# design.net
KiCad netlist of a schematic drawn in Altium Designer
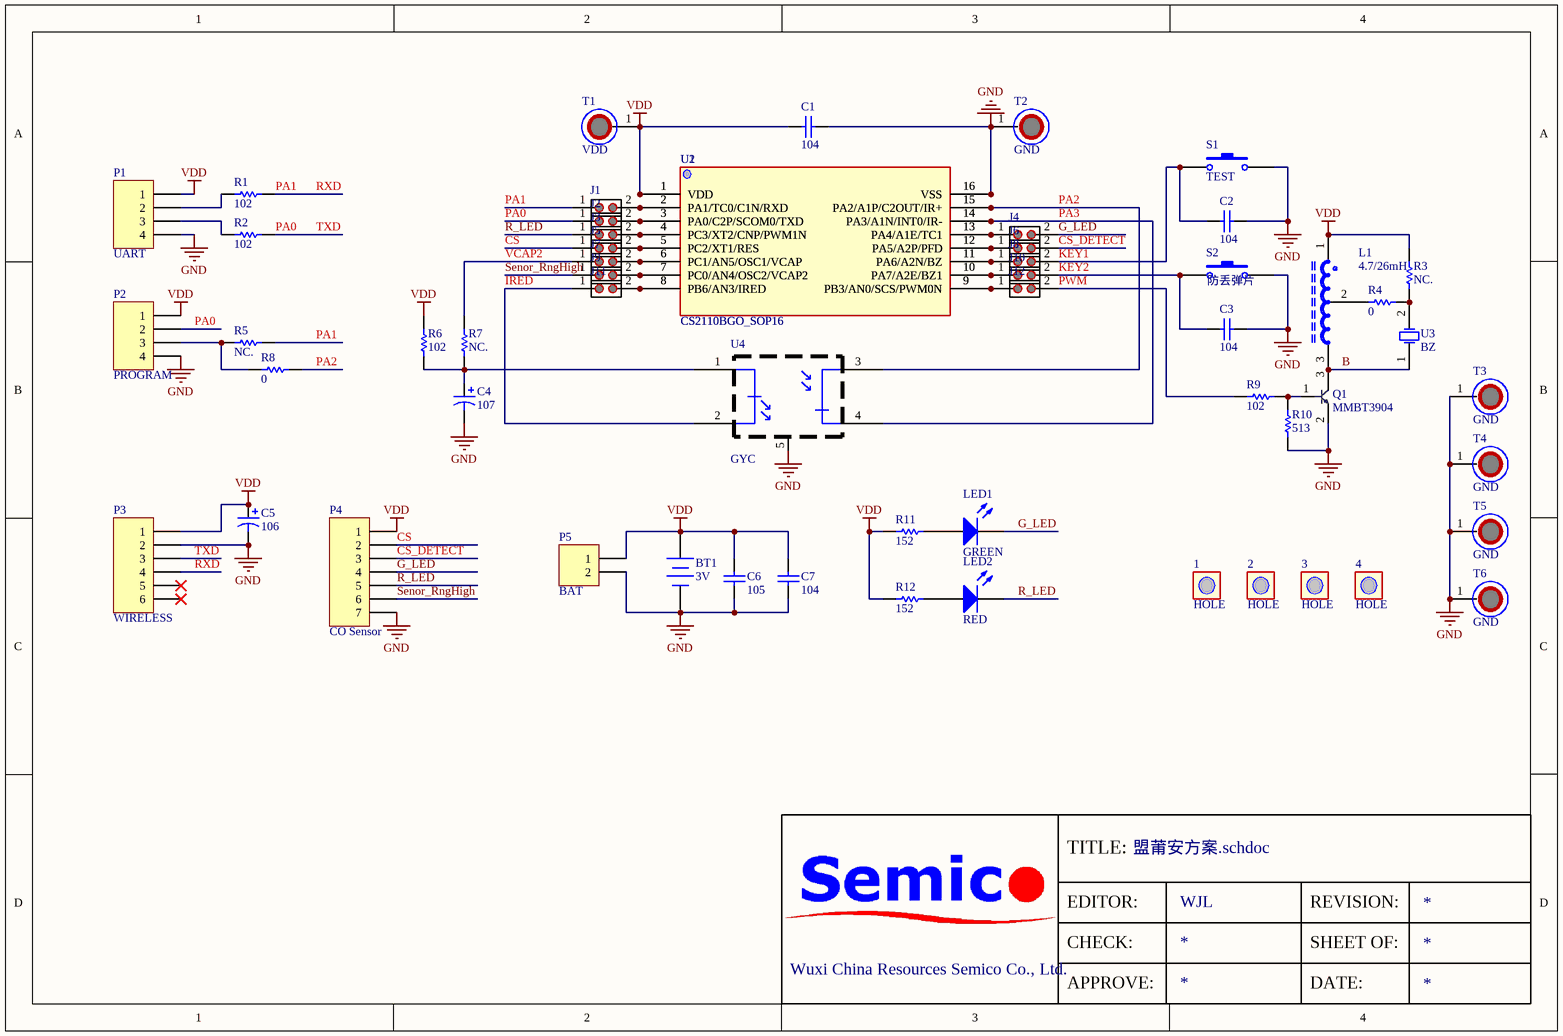
[diagram p0: 盟莆安方案.schdoc]

(export (version "E")
  (design (tool "Eeschema 10.0.6"))
  (components
    (comp (ref "1") (value "HOLE") (footprint "HOLE") (libsource (lib "原理图库") (part "HOLE")))
    (comp (ref "2") (value "HOLE") (footprint "HOLE") (libsource (lib "原理图库") (part "HOLE")))
    (comp (ref "3") (value "HOLE") (footprint "HOLE") (libsource (lib "原理图库") (part "HOLE")))
    (comp (ref "4") (value "HOLE") (footprint "HOLE") (libsource (lib "原理图库") (part "HOLE")))
    (comp (ref "BT1")
      (value "3V")
      (footprint "BAT-2")
      (description "Multicell Battery")
      (fields (field (name "PUBLISHER") "Altium Limited"))
      (libsource (lib "Miscellaneous Devices") (part "Battery"))
    )
    (comp (ref "C1")
      (value "104")
      (footprint "C0805")
      (description "Capacitor")
      (fields (field (name "PUBLISHER") "Altium Limited"))
      (libsource (lib "Miscellaneous Devices") (part "Cap"))
    )
    (comp (ref "C2")
      (value "104")
      (footprint "C0805")
      (description "Capacitor")
      (fields (field (name "PUBLISHER") "Altium Limited"))
      (libsource (lib "Miscellaneous Devices") (part "Cap"))
    )
    (comp (ref "C3")
      (value "104")
      (footprint "C0805")
      (description "Capacitor")
      (fields (field (name "PUBLISHER") "Altium Limited"))
      (libsource (lib "Miscellaneous Devices") (part "Cap"))
    )
    (comp (ref "C4")
      (value "107")
      (footprint "220UF/16V")
      (description "Polarized Capacitor (Radial)")
      (fields (field (name "PUBLISHER") "Altium Limited"))
      (libsource (lib "Miscellaneous Devices") (part "Cap Pol1"))
    )
    (comp (ref "C5")
      (value "106")
      (footprint "47UF/25V")
      (description "Polarized Capacitor (Radial)")
      (fields (field (name "PUBLISHER") "Altium Limited"))
      (libsource (lib "Miscellaneous Devices") (part "Cap Pol1"))
    )
    (comp (ref "C6")
      (value "105")
      (footprint "C0805")
      (description "Capacitor")
      (fields (field (name "PUBLISHER") "Altium Limited"))
      (libsource (lib "Miscellaneous Devices") (part "Cap"))
    )
    (comp (ref "C7")
      (value "104")
      (footprint "C0805")
      (description "Capacitor")
      (fields (field (name "PUBLISHER") "Altium Limited"))
      (libsource (lib "Miscellaneous Devices") (part "Cap"))
    )
    (comp (ref "J1") (value "~") (footprint "SIP2") (libsource (lib "原理图库") (part "JUMPER(SIP2)")))
    (comp (ref "J2") (value "~") (footprint "SIP2") (libsource (lib "原理图库") (part "JUMPER(SIP2)")))
    (comp (ref "J3") (value "~") (footprint "SIP2") (libsource (lib "原理图库") (part "JUMPER(SIP2)")))
    (comp (ref "J4") (value "~") (footprint "SIP2") (libsource (lib "原理图库") (part "JUMPER(SIP2)")))
    (comp (ref "J5") (value "~") (footprint "SIP2") (libsource (lib "原理图库") (part "JUMPER(SIP2)")))
    (comp (ref "J6") (value "~") (footprint "SIP2") (libsource (lib "原理图库") (part "JUMPER(SIP2)")))
    (comp (ref "J7") (value "~") (footprint "SIP2") (libsource (lib "原理图库") (part "JUMPER(SIP2)")))
    (comp (ref "J8") (value "~") (footprint "SIP2") (libsource (lib "原理图库") (part "JUMPER(SIP2)")))
    (comp (ref "J9") (value "~") (footprint "SIP2") (libsource (lib "原理图库") (part "JUMPER(SIP2)")))
    (comp (ref "J10") (value "~") (footprint "SIP2") (libsource (lib "原理图库") (part "JUMPER(SIP2)")))
    (comp (ref "J11") (value "~") (footprint "SIP2") (libsource (lib "原理图库") (part "JUMPER(SIP2)")))
    (comp (ref "J12") (value "~") (footprint "SIP2") (libsource (lib "原理图库") (part "JUMPER(SIP2)")))
    (comp (ref "L1")
      (value "4.7/26mH")
      (footprint "LGB3W0912")
      (libsource (lib "原理图库") (part "Inductor - 3"))
    )
    (comp (ref "LED1")
      (value "GREEN")
      (footprint "L0805")
      (description "Typical INFRARED GaAs LED")
      (fields (field (name "PUBLISHER") "Altium Limited"))
      (libsource (lib "Miscellaneous Devices") (part "LED0"))
    )
    (comp (ref "LED2")
      (value "RED")
      (footprint "L0805")
      (description "Typical INFRARED GaAs LED")
      (fields (field (name "PUBLISHER") "Altium Limited"))
      (libsource (lib "Miscellaneous Devices") (part "LED0"))
    )
    (comp (ref "P1")
      (value "UART")
      (footprint "HDR1X4")
      (description "Header, 4-Pin")
      (fields (field (name "PUBLISHER") "Altium Limited"))
      (libsource (lib "Miscellaneous Connectors") (part "Header 4"))
    )
    (comp (ref "P2")
      (value "PROGRAM")
      (footprint "HDR1X4")
      (description "Header, 4-Pin")
      (fields (field (name "PUBLISHER") "Altium Limited"))
      (libsource (lib "Miscellaneous Connectors") (part "Header 4"))
    )
    (comp (ref "P3")
      (value "WIRELESS")
      (footprint "HDR1X6")
      (description "Header, 6-Pin")
      (fields (field (name "PUBLISHER") "Altium Limited"))
      (libsource (lib "Miscellaneous Connectors") (part "Header 6"))
    )
    (comp (ref "P4")
      (value "CO Sensor")
      (footprint "HDR1X7")
      (description "Header, 7-Pin")
      (fields (field (name "PUBLISHER") "Altium Limited"))
      (libsource (lib "Miscellaneous Connectors") (part "Header 7"))
    )
    (comp (ref "P5")
      (value "BAT")
      (footprint "CS2110 FULL FUNCTION:3.81-02P")
      (description "Header, 2-Pin")
      (fields (field (name "PUBLISHER") "Altium Limited"))
      (libsource (lib "Miscellaneous Connectors") (part "Header 2"))
    )
    (comp (ref "Q1") (value "MMBT3904") (footprint "MMBT3906") (libsource (lib "原理图库") (part "NPN")))
    (comp (ref "R1")
      (value "102")
      (footprint "0805")
      (description "Resistor")
      (fields (field (name "PUBLISHER") "Altium Limited"))
      (libsource (lib "Miscellaneous Devices") (part "Res1"))
    )
    (comp (ref "R2")
      (value "102")
      (footprint "0805")
      (description "Resistor")
      (fields (field (name "PUBLISHER") "Altium Limited"))
      (libsource (lib "Miscellaneous Devices") (part "Res1"))
    )
    (comp (ref "R3")
      (value "NC.")
      (footprint "0805")
      (description "Resistor")
      (fields (field (name "PUBLISHER") "Altium Limited"))
      (libsource (lib "Miscellaneous Devices") (part "Res1"))
    )
    (comp (ref "R4")
      (value "0")
      (footprint "0805")
      (description "Resistor")
      (fields (field (name "PUBLISHER") "Altium Limited"))
      (libsource (lib "Miscellaneous Devices") (part "Res1"))
    )
    (comp (ref "R5")
      (value "NC.")
      (footprint "0805")
      (description "Resistor")
      (fields (field (name "PUBLISHER") "Altium Limited"))
      (libsource (lib "Miscellaneous Devices") (part "Res1"))
    )
    (comp (ref "R6")
      (value "102")
      (footprint "0805")
      (description "Resistor")
      (fields (field (name "PUBLISHER") "Altium Limited"))
      (libsource (lib "Miscellaneous Devices") (part "Res1"))
    )
    (comp (ref "R7")
      (value "NC.")
      (footprint "0805")
      (description "Resistor")
      (fields (field (name "PUBLISHER") "Altium Limited"))
      (libsource (lib "Miscellaneous Devices") (part "Res1"))
    )
    (comp (ref "R8")
      (value "0")
      (footprint "0805")
      (description "Resistor")
      (fields (field (name "PUBLISHER") "Altium Limited"))
      (libsource (lib "Miscellaneous Devices") (part "Res1"))
    )
    (comp (ref "R9")
      (value "102")
      (footprint "0805")
      (description "Resistor")
      (fields (field (name "PUBLISHER") "Altium Limited"))
      (libsource (lib "Miscellaneous Devices") (part "Res1"))
    )
    (comp (ref "R10")
      (value "513")
      (footprint "0805")
      (description "Resistor")
      (fields (field (name "PUBLISHER") "Altium Limited"))
      (libsource (lib "Miscellaneous Devices") (part "Res1"))
    )
    (comp (ref "R11")
      (value "152")
      (footprint "0805")
      (description "Resistor")
      (fields (field (name "PUBLISHER") "Altium Limited"))
      (libsource (lib "Miscellaneous Devices") (part "Res1"))
    )
    (comp (ref "R12")
      (value "152")
      (footprint "0805")
      (description "Resistor")
      (fields (field (name "PUBLISHER") "Altium Limited"))
      (libsource (lib "Miscellaneous Devices") (part "Res1"))
    )
    (comp (ref "S1")
      (value "TEST")
      (footprint "KEYP")
      (description "Switch")
      (fields (field (name "PUBLISHER") "Altium Limited"))
      (libsource (lib "Miscellaneous Devices") (part "SW-PB"))
    )
    (comp (ref "S2")
      (value "~")
      (footprint "KEYP")
      (description "Switch")
      (fields (field (name "PUBLISHER") "Altium Limited"))
      (libsource (lib "Miscellaneous Devices") (part "SW-PB"))
    )
    (comp (ref "T1") (value "VDD") (footprint "TEST POINT") (libsource (lib "原理图库") (part "TEST POINT")))
    (comp (ref "T2") (value "GND") (footprint "TEST POINT") (libsource (lib "原理图库") (part "TEST POINT")))
    (comp (ref "T3") (value "GND") (footprint "TEST POINT") (libsource (lib "原理图库") (part "TEST POINT")))
    (comp (ref "T4") (value "GND") (footprint "TEST POINT") (libsource (lib "原理图库") (part "TEST POINT")))
    (comp (ref "T5") (value "GND") (footprint "TEST POINT") (libsource (lib "原理图库") (part "TEST POINT")))
    (comp (ref "T6") (value "GND") (footprint "TEST POINT") (libsource (lib "原理图库") (part "TEST POINT")))
    (comp (ref "U1")
      (value "CS2110BGO_SOP16")
      (footprint "SOP16")
      (libsource (lib "原理图库") (part "CS2110AGO_SOP16"))
    )
    (comp (ref "U2")
      (value "CS2110BGO_SOP16")
      (footprint "TSOP16底座")
      (libsource (lib "原理图库") (part "CS2110AGO_SOP16"))
    )
    (comp (ref "U3")
      (value "BZ")
      (footprint "SMD-BZ - 4")
      (description "Crystal Oscillator")
      (fields (field (name "PUBLISHER") "Altium Limited"))
      (libsource (lib "Miscellaneous Devices") (part "XTAL"))
    )
    (comp (ref "U4") (value "GYC") (footprint "YANCANG1") (libsource (lib "原理图库") (part "感烟仓")))
  )
  (nets
    (net (code "1") (name "/B") (class "Default")
      (node (ref "L1") (pin "3") (pinfunction "3_3") (pintype "passive"))
      (node (ref "Q1") (pin "3") (pinfunction "C_3") (pintype "passive"))
      (node (ref "U3") (pin "1") (pinfunction "OSC1_1") (pintype "passive"))
    )
    (net (code "2") (name "/CS") (class "Default")
      (node (ref "J5") (pin "1") (pinfunction "1_1") (pintype "passive"))
      (node (ref "P4") (pin "2") (pinfunction "2_2") (pintype "passive"))
    )
    (net (code "3") (name "/CS_DETECT") (class "Default")
      (node (ref "J6") (pin "2") (pinfunction "2_2") (pintype "passive"))
      (node (ref "P4") (pin "3") (pinfunction "3_3") (pintype "passive"))
    )
    (net (code "4") (name "/G_LED") (class "Default")
      (node (ref "J4") (pin "2") (pinfunction "2_2") (pintype "passive"))
      (node (ref "LED1") (pin "2") (pinfunction "K_2") (pintype "passive"))
      (node (ref "P4") (pin "4") (pinfunction "4_4") (pintype "passive"))
    )
    (net (code "5") (name "/IRED") (class "Default")
      (node (ref "J11") (pin "1") (pinfunction "1_1") (pintype "passive"))
      (node (ref "U4") (pin "2") (pintype "passive"))
    )
    (net (code "6") (name "/KEY1") (class "Default")
      (node (ref "C2") (pin "1") (pinfunction "1_1") (pintype "passive"))
      (node (ref "J8") (pin "2") (pinfunction "2_2") (pintype "passive"))
      (node (ref "S1") (pin "1") (pinfunction "1_1") (pintype "passive"))
    )
    (net (code "7") (name "/KEY2") (class "Default")
      (node (ref "C3") (pin "1") (pinfunction "1_1") (pintype "passive"))
      (node (ref "J10") (pin "2") (pinfunction "2_2") (pintype "passive"))
      (node (ref "S2") (pin "1") (pinfunction "1_1") (pintype "passive"))
    )
    (net (code "8") (name "/PA0") (class "Default")
      (node (ref "J2") (pin "1") (pinfunction "1_1") (pintype "passive"))
      (node (ref "P2") (pin "2") (pinfunction "2_2") (pintype "passive"))
      (node (ref "P3") (pin "3") (pinfunction "3_3") (pintype "passive"))
      (node (ref "R2") (pin "1") (pinfunction "1_1") (pintype "passive"))
    )
    (net (code "9") (name "/PA1") (class "Default")
      (node (ref "J1") (pin "1") (pinfunction "1_1") (pintype "passive"))
      (node (ref "P3") (pin "4") (pinfunction "4_4") (pintype "passive"))
      (node (ref "R1") (pin "1") (pinfunction "1_1") (pintype "passive"))
      (node (ref "R5") (pin "1") (pinfunction "1_1") (pintype "passive"))
    )
    (net (code "10") (name "/PA2") (class "Default")
      (node (ref "R8") (pin "1") (pinfunction "1_1") (pintype "passive"))
      (node (ref "U1") (pin "15") (pinfunction "PA2/A1P/C2OUT/IR+_15") (pintype "passive"))
      (node (ref "U2") (pin "15") (pinfunction "PA2/A1P/C2OUT/IR+_15") (pintype "passive"))
      (node (ref "U4") (pin "3") (pintype "passive"))
    )
    (net (code "11") (name "/PA3") (class "Default")
      (node (ref "U1") (pin "14") (pinfunction "PA3/A1N/INT0/IR-_14") (pintype "passive"))
      (node (ref "U2") (pin "14") (pinfunction "PA3/A1N/INT0/IR-_14") (pintype "passive"))
      (node (ref "U4") (pin "4") (pintype "passive"))
    )
    (net (code "12") (name "/PWM") (class "Default")
      (node (ref "J12") (pin "2") (pinfunction "2_2") (pintype "passive"))
      (node (ref "R9") (pin "2") (pinfunction "2_2") (pintype "passive"))
    )
    (net (code "13") (name "/R_LED") (class "Default")
      (node (ref "J3") (pin "1") (pinfunction "1_1") (pintype "passive"))
      (node (ref "LED2") (pin "2") (pinfunction "K_2") (pintype "passive"))
      (node (ref "P4") (pin "5") (pinfunction "5_5") (pintype "passive"))
    )
    (net (code "14") (name "/Senor_RngHigh") (class "Default")
      (node (ref "J9") (pin "1") (pinfunction "1_1") (pintype "passive"))
      (node (ref "P4") (pin "6") (pinfunction "6_6") (pintype "passive"))
    )
    (net (code "15") (name "/VCAP2") (class "Default")
      (node (ref "J7") (pin "1") (pinfunction "1_1") (pintype "passive"))
      (node (ref "R7") (pin "1") (pinfunction "1_1") (pintype "passive"))
    )
    (net (code "16") (name "GND") (class "Default")
      (node (ref "BT1") (pin "2") (pinfunction "-_2") (pintype "passive"))
      (node (ref "C1") (pin "1") (pinfunction "1_1") (pintype "passive"))
      (node (ref "C2") (pin "2") (pinfunction "2_2") (pintype "passive"))
      (node (ref "C3") (pin "2") (pinfunction "2_2") (pintype "passive"))
      (node (ref "C4") (pin "2") (pinfunction "2_2") (pintype "passive"))
      (node (ref "C5") (pin "2") (pinfunction "2_2") (pintype "passive"))
      (node (ref "C6") (pin "2") (pinfunction "2_2") (pintype "passive"))
      (node (ref "C7") (pin "2") (pinfunction "2_2") (pintype "passive"))
      (node (ref "P1") (pin "4") (pinfunction "4_4") (pintype "passive"))
      (node (ref "P2") (pin "4") (pinfunction "4_4") (pintype "passive"))
      (node (ref "P3") (pin "2") (pinfunction "2_2") (pintype "passive"))
      (node (ref "P4") (pin "7") (pinfunction "7_7") (pintype "passive"))
      (node (ref "P5") (pin "2") (pinfunction "2_2") (pintype "passive"))
      (node (ref "Q1") (pin "2") (pinfunction "E_2") (pintype "passive"))
      (node (ref "R10") (pin "1") (pinfunction "1_1") (pintype "passive"))
      (node (ref "S1") (pin "2") (pinfunction "2_2") (pintype "passive"))
      (node (ref "S2") (pin "2") (pinfunction "2_2") (pintype "passive"))
      (node (ref "T2") (pin "1") (pinfunction "1_1") (pintype "passive"))
      (node (ref "T3") (pin "1") (pinfunction "1_1") (pintype "passive"))
      (node (ref "T4") (pin "1") (pinfunction "1_1") (pintype "passive"))
      (node (ref "T5") (pin "1") (pinfunction "1_1") (pintype "passive"))
      (node (ref "T6") (pin "1") (pinfunction "1_1") (pintype "passive"))
      (node (ref "U1") (pin "16") (pinfunction "VSS_16") (pintype "passive"))
      (node (ref "U2") (pin "16") (pinfunction "VSS_16") (pintype "passive"))
      (node (ref "U4") (pin "5") (pinfunction "GND_5") (pintype "passive"))
    )
    (net (code "17") (name "Net-(C4-Pad1)") (class "Default")
      (node (ref "C4") (pin "1") (pinfunction "1_1") (pintype "passive"))
      (node (ref "R6") (pin "2") (pinfunction "2_2") (pintype "passive"))
      (node (ref "R7") (pin "2") (pinfunction "2_2") (pintype "passive"))
      (node (ref "U4") (pin "1") (pintype "passive"))
    )
    (net (code "18") (name "Net-(L1-Pad2)") (class "Default")
      (node (ref "L1") (pin "2") (pinfunction "2_2") (pintype "passive"))
      (node (ref "R4") (pin "1") (pinfunction "1_1") (pintype "passive"))
    )
    (net (code "19") (name "Net-(LED1-A)") (class "Default")
      (node (ref "LED1") (pin "1") (pinfunction "A_1") (pintype "passive"))
      (node (ref "R11") (pin "1") (pinfunction "1_1") (pintype "passive"))
    )
    (net (code "20") (name "Net-(LED2-A)") (class "Default")
      (node (ref "LED2") (pin "1") (pinfunction "A_1") (pintype "passive"))
      (node (ref "R12") (pin "1") (pinfunction "1_1") (pintype "passive"))
    )
    (net (code "21") (name "Net-(P1-Pad2)") (class "Default")
      (node (ref "P1") (pin "2") (pinfunction "2_2") (pintype "passive"))
      (node (ref "R1") (pin "2") (pinfunction "2_2") (pintype "passive"))
    )
    (net (code "22") (name "Net-(P1-Pad3)") (class "Default")
      (node (ref "P1") (pin "3") (pinfunction "3_3") (pintype "passive"))
      (node (ref "R2") (pin "2") (pinfunction "2_2") (pintype "passive"))
    )
    (net (code "23") (name "Net-(P2-Pad3)") (class "Default")
      (node (ref "P2") (pin "3") (pinfunction "3_3") (pintype "passive"))
      (node (ref "R5") (pin "2") (pinfunction "2_2") (pintype "passive"))
      (node (ref "R8") (pin "2") (pinfunction "2_2") (pintype "passive"))
    )
    (net (code "24") (name "Net-(Q1-B)") (class "Default")
      (node (ref "Q1") (pin "1") (pinfunction "B_1") (pintype "passive"))
      (node (ref "R10") (pin "2") (pinfunction "2_2") (pintype "passive"))
      (node (ref "R9") (pin "1") (pinfunction "1_1") (pintype "passive"))
    )
    (net (code "25") (name "Net-(U1-PA0{slash}C2P{slash}SCOM0{slash}TXD)") (class "Default")
      (node (ref "J2") (pin "2") (pinfunction "2_2") (pintype "passive"))
      (node (ref "U1") (pin "3") (pinfunction "PA0/C2P/SCOM0/TXD_3") (pintype "passive"))
      (node (ref "U2") (pin "3") (pinfunction "PA0/C2P/SCOM0/TXD_3") (pintype "passive"))
    )
    (net (code "26") (name "Net-(U1-PA1{slash}TC0{slash}C1N{slash}RXD)") (class "Default")
      (node (ref "J1") (pin "2") (pinfunction "2_2") (pintype "passive"))
      (node (ref "U1") (pin "2") (pinfunction "PA1/TC0/C1N/RXD_2") (pintype "passive"))
      (node (ref "U2") (pin "2") (pinfunction "PA1/TC0/C1N/RXD_2") (pintype "passive"))
    )
    (net (code "27") (name "Net-(U1-PA4{slash}A1E{slash}TC1)") (class "Default")
      (node (ref "J4") (pin "1") (pinfunction "1_1") (pintype "passive"))
      (node (ref "U1") (pin "13") (pinfunction "PA4/A1E/TC1_13") (pintype "passive"))
      (node (ref "U2") (pin "13") (pinfunction "PA4/A1E/TC1_13") (pintype "passive"))
    )
    (net (code "28") (name "Net-(U1-PA5{slash}A2P{slash}PFD)") (class "Default")
      (node (ref "J6") (pin "1") (pinfunction "1_1") (pintype "passive"))
      (node (ref "U1") (pin "12") (pinfunction "PA5/A2P/PFD_12") (pintype "passive"))
      (node (ref "U2") (pin "12") (pinfunction "PA5/A2P/PFD_12") (pintype "passive"))
    )
    (net (code "29") (name "Net-(U1-PA6{slash}A2N{slash}BZ)") (class "Default")
      (node (ref "J8") (pin "1") (pinfunction "1_1") (pintype "passive"))
      (node (ref "U1") (pin "11") (pinfunction "PA6/A2N/BZ_11") (pintype "passive"))
      (node (ref "U2") (pin "11") (pinfunction "PA6/A2N/BZ_11") (pintype "passive"))
    )
    (net (code "30") (name "Net-(U1-PA7{slash}A2E{slash}BZ1)") (class "Default")
      (node (ref "J10") (pin "1") (pinfunction "1_1") (pintype "passive"))
      (node (ref "U1") (pin "10") (pinfunction "PA7/A2E/BZ1_10") (pintype "passive"))
      (node (ref "U2") (pin "10") (pinfunction "PA7/A2E/BZ1_10") (pintype "passive"))
    )
    (net (code "31") (name "Net-(U1-PB3{slash}AN0{slash}SCS{slash}PWM0N)") (class "Default")
      (node (ref "J12") (pin "1") (pinfunction "1_1") (pintype "passive"))
      (node (ref "U1") (pin "9") (pinfunction "PB3/AN0/SCS/PWM0N_9") (pintype "passive"))
      (node (ref "U2") (pin "9") (pinfunction "PB3/AN0/SCS/PWM0N_9") (pintype "passive"))
    )
    (net (code "32") (name "Net-(U1-PB6{slash}AN3{slash}IRED)") (class "Default")
      (node (ref "J11") (pin "2") (pinfunction "2_2") (pintype "passive"))
      (node (ref "U1") (pin "8") (pinfunction "PB6/AN3/IRED_8") (pintype "passive"))
      (node (ref "U2") (pin "8") (pinfunction "PB6/AN3/IRED_8") (pintype "passive"))
    )
    (net (code "33") (name "Net-(U1-PC0{slash}AN4{slash}OSC2{slash}VCAP2)") (class "Default")
      (node (ref "J9") (pin "2") (pinfunction "2_2") (pintype "passive"))
      (node (ref "U1") (pin "7") (pinfunction "PC0/AN4/OSC2/VCAP2_7") (pintype "passive"))
      (node (ref "U2") (pin "7") (pinfunction "PC0/AN4/OSC2/VCAP2_7") (pintype "passive"))
    )
    (net (code "34") (name "Net-(U1-PC1{slash}AN5{slash}OSC1{slash}VCAP)") (class "Default")
      (node (ref "J7") (pin "2") (pinfunction "2_2") (pintype "passive"))
      (node (ref "U1") (pin "6") (pinfunction "PC1/AN5/OSC1/VCAP_6") (pintype "passive"))
      (node (ref "U2") (pin "6") (pinfunction "PC1/AN5/OSC1/VCAP_6") (pintype "passive"))
    )
    (net (code "35") (name "Net-(U1-PC2{slash}XT1{slash}RES)") (class "Default")
      (node (ref "J5") (pin "2") (pinfunction "2_2") (pintype "passive"))
      (node (ref "U1") (pin "5") (pinfunction "PC2/XT1/RES_5") (pintype "passive"))
      (node (ref "U2") (pin "5") (pinfunction "PC2/XT1/RES_5") (pintype "passive"))
    )
    (net (code "36") (name "Net-(U1-PC3{slash}XT2{slash}CNP{slash}PWM1N)") (class "Default")
      (node (ref "J3") (pin "2") (pinfunction "2_2") (pintype "passive"))
      (node (ref "U1") (pin "4") (pinfunction "PC3/XT2/CNP/PWM1N_4") (pintype "passive"))
      (node (ref "U2") (pin "4") (pinfunction "PC3/XT2/CNP/PWM1N_4") (pintype "passive"))
    )
    (net (code "37") (name "Net-(U3-OSC2)") (class "Default")
      (node (ref "R3") (pin "2") (pinfunction "2_2") (pintype "passive"))
      (node (ref "R4") (pin "2") (pinfunction "2_2") (pintype "passive"))
      (node (ref "U3") (pin "2") (pinfunction "OSC2_2") (pintype "passive"))
    )
    (net (code "38") (name "VDD") (class "Default")
      (node (ref "BT1") (pin "1") (pinfunction "+_1") (pintype "passive"))
      (node (ref "C1") (pin "2") (pinfunction "2_2") (pintype "passive"))
      (node (ref "C5") (pin "1") (pinfunction "1_1") (pintype "passive"))
      (node (ref "C6") (pin "1") (pinfunction "1_1") (pintype "passive"))
      (node (ref "C7") (pin "1") (pinfunction "1_1") (pintype "passive"))
      (node (ref "L1") (pin "1") (pinfunction "1_1") (pintype "passive"))
      (node (ref "P1") (pin "1") (pinfunction "1_1") (pintype "passive"))
      (node (ref "P2") (pin "1") (pinfunction "1_1") (pintype "passive"))
      (node (ref "P3") (pin "1") (pinfunction "1_1") (pintype "passive"))
      (node (ref "P4") (pin "1") (pinfunction "1_1") (pintype "passive"))
      (node (ref "P5") (pin "1") (pinfunction "1_1") (pintype "passive"))
      (node (ref "R11") (pin "2") (pinfunction "2_2") (pintype "passive"))
      (node (ref "R12") (pin "2") (pinfunction "2_2") (pintype "passive"))
      (node (ref "R3") (pin "1") (pinfunction "1_1") (pintype "passive"))
      (node (ref "R6") (pin "1") (pinfunction "1_1") (pintype "passive"))
      (node (ref "T1") (pin "1") (pinfunction "1_1") (pintype "passive"))
      (node (ref "U1") (pin "1") (pinfunction "VDD_1") (pintype "passive"))
      (node (ref "U2") (pin "1") (pinfunction "VDD_1") (pintype "passive"))
    )
    (net (code "39") (name "unconnected-(P3-Pad5)") (class "Default")
      (node (ref "P3") (pin "5") (pinfunction "5_5") (pintype "passive+no_connect"))
    )
    (net (code "40") (name "unconnected-(P3-Pad6)") (class "Default")
      (node (ref "P3") (pin "6") (pinfunction "6_6") (pintype "passive+no_connect"))
    )
  )
)
